# panel_board.net
KiCad netlist of a schematic drawn in Altium Designer
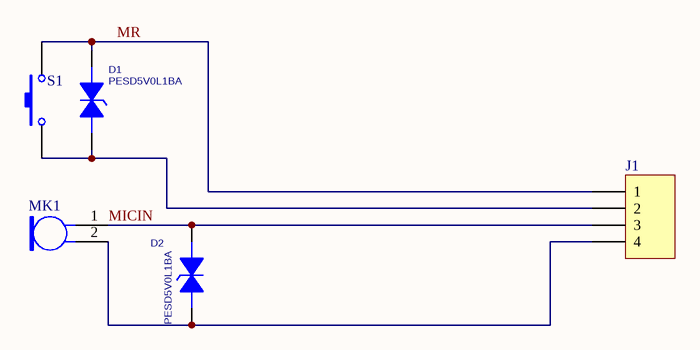
[diagram p0: panel_board.SchDoc]

(export (version "E")
  (design (tool "Eeschema 10.0.6"))
  (components
    (comp (ref "D1") (value "PESD5V0L1BA") (libsource (lib "*") (part "PESD")))
    (comp (ref "D2") (value "PESD5V0L1BA") (libsource (lib "*") (part "PESD")))
    (comp (ref "J1")
      (value "MIC & RST-PB")
      (footprint "FPC1.0-DR-SMD-4P-F2.0")
      (description "Header, 4-Pin")
      (fields (field (name "PUBLISHER") "Altium Limited"))
      (libsource (lib "Miscellaneous Connectors") (part "Header 4"))
    )
    (comp (ref "MK1")
      (value "Mic2")
      (footprint "MIC4015")
      (description "Microphone")
      (fields (field (name "PUBLISHER") "Altium Limited"))
      (libsource (lib "Miscellaneous Devices") (part "Mic2"))
    )
    (comp (ref "S1")
      (value "SW-PB")
      (footprint "SW-PB-SMD")
      (description "Switch")
      (fields (field (name "PUBLISHER") "Altium Limited"))
      (libsource (lib "Miscellaneous Devices") (part "SW-PB"))
    )
  )
  (nets
    (net (code "1") (name "/MICIN") (class "Default")
      (node (ref "D2") (pin "2") (pinfunction "2_2") (pintype "passive"))
      (node (ref "J1") (pin "3") (pinfunction "3_3") (pintype "passive"))
      (node (ref "MK1") (pin "1") (pinfunction "1_1") (pintype "passive"))
    )
    (net (code "2") (name "/MR") (class "Default")
      (node (ref "D1") (pin "2") (pinfunction "2_2") (pintype "passive"))
      (node (ref "J1") (pin "1") (pinfunction "1_1") (pintype "passive"))
      (node (ref "S1") (pin "1") (pinfunction "1_1") (pintype "passive"))
    )
    (net (code "3") (name "Net-(D1-Pad1)") (class "Default")
      (node (ref "D1") (pin "1") (pinfunction "1_1") (pintype "passive"))
      (node (ref "J1") (pin "2") (pinfunction "2_2") (pintype "passive"))
      (node (ref "S1") (pin "2") (pinfunction "2_2") (pintype "passive"))
    )
    (net (code "4") (name "Net-(D2-Pad1)") (class "Default")
      (node (ref "D2") (pin "1") (pinfunction "1_1") (pintype "passive"))
      (node (ref "J1") (pin "4") (pinfunction "4_4") (pintype "passive"))
      (node (ref "MK1") (pin "2") (pinfunction "2_2") (pintype "passive"))
    )
  )
)
